# 02_TFT_LED.net
KiCad netlist of a schematic drawn in Altium Designer
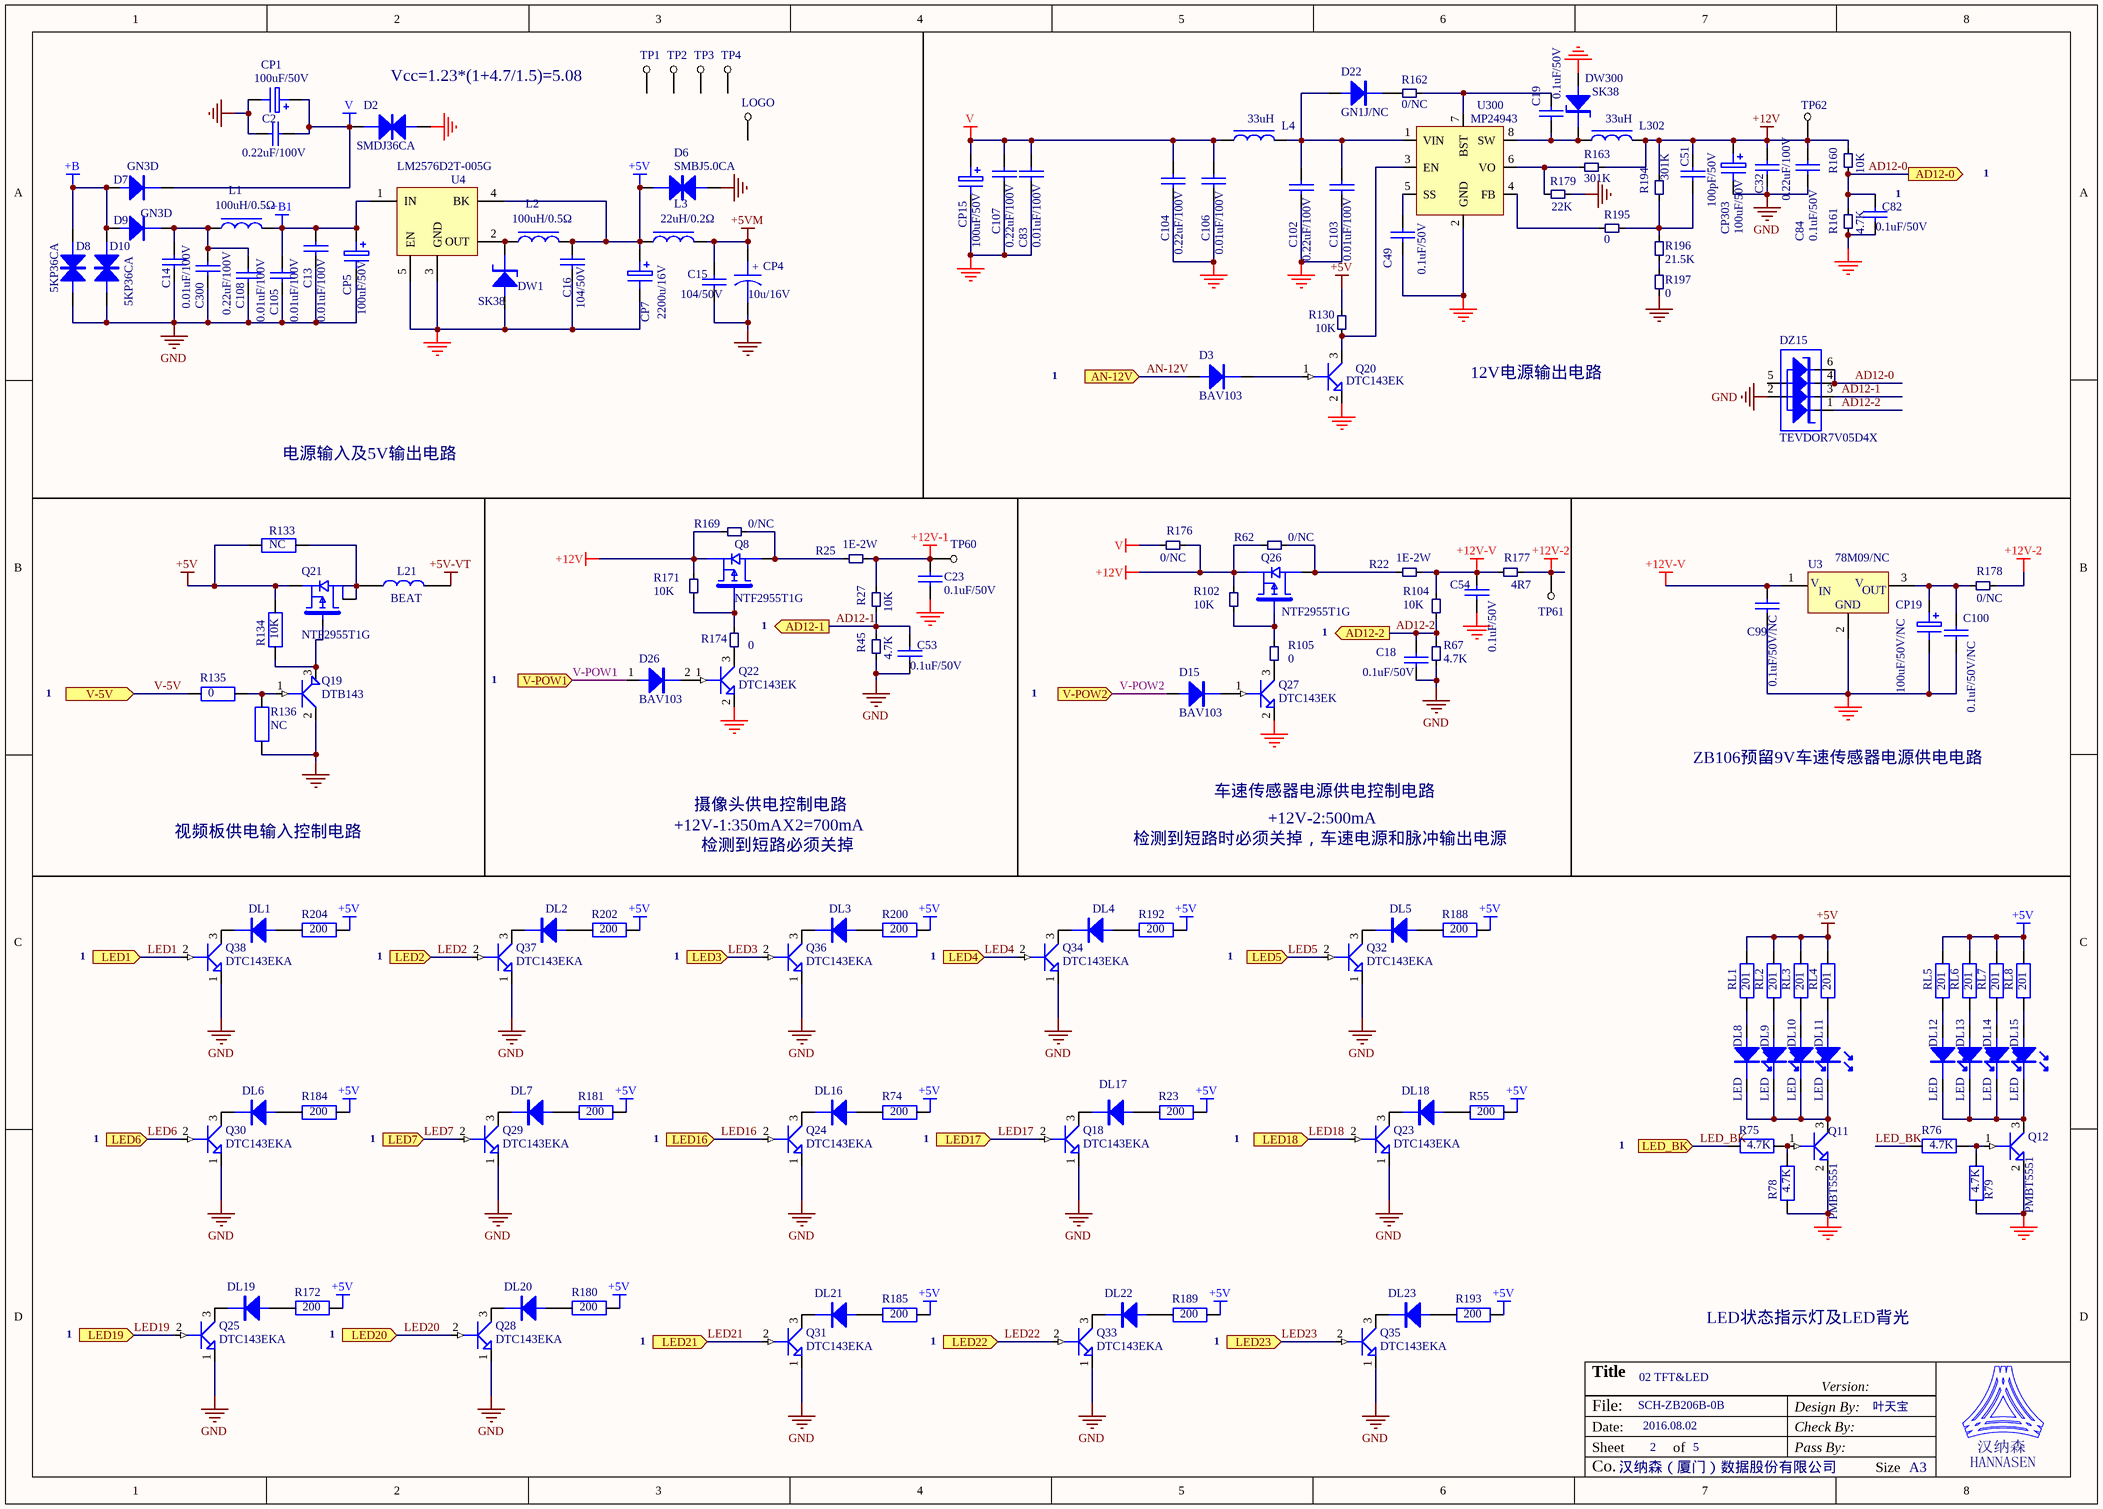
[diagram p0: 02 TFT&LED.SchDoc]

(export (version "E")
  (design (tool "Eeschema 10.0.6"))
  (components
    (comp (ref "C2")
      (value "0.22uF/100V")
      (footprint "CR1206")
      (description "Capacitor")
      (libsource (lib "*") (part "CAP"))
    )
    (comp (ref "C13")
      (value "0.01uF/100V")
      (footprint "CR0805")
      (description "Capacitor")
      (libsource (lib "*") (part "CAP"))
    )
    (comp (ref "C14")
      (value "0.01uF/100V")
      (footprint "CR0805")
      (description "Capacitor")
      (libsource (lib "*") (part "CAP"))
    )
    (comp (ref "C15")
      (value "104/50V")
      (footprint "CR0805")
      (description "Capacitor")
      (libsource (lib "*") (part "CAP"))
    )
    (comp (ref "C16")
      (value "104/50V")
      (footprint "CR0805")
      (description "Capacitor")
      (libsource (lib "*") (part "CAP"))
    )
    (comp (ref "C18")
      (value "0.1uF/50V")
      (footprint "CR0805")
      (description "Capacitor")
      (libsource (lib "*") (part "CAP"))
    )
    (comp (ref "C19")
      (value "0.1uF/50V")
      (footprint "CR0805")
      (description "Capacitor")
      (libsource (lib "*") (part "CAP"))
    )
    (comp (ref "C23")
      (value "0.1uF/50V")
      (footprint "CR0805")
      (description "Capacitor")
      (libsource (lib "*") (part "CAP"))
    )
    (comp (ref "C32")
      (value "0.22uF/100V")
      (footprint "CR1206")
      (description "Capacitor")
      (libsource (lib "*") (part "CAP"))
    )
    (comp (ref "C49")
      (value "0.1uF/50V")
      (footprint "CR0805")
      (description "Capacitor")
      (libsource (lib "*") (part "CAP"))
    )
    (comp (ref "C51")
      (value "100pF/50V")
      (footprint "CR0805")
      (description "Capacitor")
      (libsource (lib "*") (part "CAP"))
    )
    (comp (ref "C53")
      (value "0.1uF/50V")
      (footprint "CR0805")
      (description "Capacitor")
      (libsource (lib "*") (part "CAP"))
    )
    (comp (ref "C54")
      (value "0.1uF/50V")
      (footprint "CR0805")
      (description "Capacitor")
      (libsource (lib "*") (part "CAP"))
    )
    (comp (ref "C82")
      (value "0.1uF/50V")
      (footprint "CR0805")
      (description "Capacitor")
      (libsource (lib "*") (part "CAP"))
    )
    (comp (ref "C83")
      (value "0.01uF/100V")
      (footprint "CR0805")
      (description "Capacitor")
      (libsource (lib "*") (part "CAP"))
    )
    (comp (ref "C84")
      (value "0.1uF/50V")
      (footprint "CR0805")
      (description "Capacitor")
      (libsource (lib "*") (part "CAP"))
    )
    (comp (ref "C99")
      (value "0.1uF/50V/NC")
      (footprint "CR0805")
      (description "Capacitor")
      (libsource (lib "*") (part "CAP"))
    )
    (comp (ref "C100")
      (value "0.1uF/50V/NC")
      (footprint "CR0805")
      (description "Capacitor")
      (libsource (lib "*") (part "CAP"))
    )
    (comp (ref "C102")
      (value "0.22uF/100V")
      (footprint "CR1206")
      (description "Capacitor")
      (libsource (lib "*") (part "CAP"))
    )
    (comp (ref "C103")
      (value "0.01uF/100V")
      (footprint "CR0805")
      (description "Capacitor")
      (libsource (lib "*") (part "CAP"))
    )
    (comp (ref "C104")
      (value "0.22uF/100V")
      (footprint "CR1206")
      (description "Capacitor")
      (libsource (lib "*") (part "CAP"))
    )
    (comp (ref "C105")
      (value "0.01uF/100V")
      (footprint "CR0805")
      (description "Capacitor")
      (libsource (lib "*") (part "CAP"))
    )
    (comp (ref "C106")
      (value "0.01uF/100V")
      (footprint "CR0805")
      (description "Capacitor")
      (libsource (lib "*") (part "CAP"))
    )
    (comp (ref "C107")
      (value "0.22uF/100V")
      (footprint "CR1206")
      (description "Capacitor")
      (libsource (lib "*") (part "CAP"))
    )
    (comp (ref "C108")
      (value "0.01uF/100V")
      (footprint "CR0805")
      (description "Capacitor")
      (libsource (lib "*") (part "CAP"))
    )
    (comp (ref "C300")
      (value "0.22uF/100V")
      (footprint "CR1206")
      (description "Capacitor")
      (libsource (lib "*") (part "CAP"))
    )
    (comp (ref "CP1")
      (value "100uF/50V")
      (footprint "RB10")
      (description "电解电容")
      (libsource (lib "*") (part "ELECTRO1"))
    )
    (comp (ref "CP4")
      (value "10u/16V")
      (footprint "CE1206")
      (description "Capacitor")
      (libsource (lib "*") (part "CAPACITOR POL"))
    )
    (comp (ref "CP5")
      (value "100uF/50V")
      (footprint "RB5-1")
      (description "电解电容")
      (libsource (lib "*") (part "ELECTRO1"))
    )
    (comp (ref "CP7")
      (value "2200u/16V")
      (footprint "RB12.5")
      (description "电解电容")
      (libsource (lib "*") (part "ELECTRO1"))
    )
    (comp (ref "CP15")
      (value "100uF/50V")
      (footprint "RB5-1")
      (description "电解电容")
      (libsource (lib "*") (part "ELECTRO1"))
    )
    (comp (ref "CP19")
      (value "100uF/50V/NC")
      (footprint "RB5-1")
      (description "电解电容")
      (libsource (lib "*") (part "ELECTRO1"))
    )
    (comp (ref "CP303")
      (value "100uF/50V")
      (footprint "RB5-1")
      (description "电解电容")
      (libsource (lib "*") (part "ELECTRO1"))
    )
    (comp (ref "D2") (value "SMDJ36CA") (footprint "SMC-D") (libsource (lib "YDM-SQ-1SCH") (part "TVS")))
    (comp (ref "D3")
      (value "BAV103")
      (footprint "SOD-80C")
      (description "二极管")
      (libsource (lib "*") (part "DIODE"))
    )
    (comp (ref "D6") (value "SMBJ5.0CA") (footprint "SMB-D") (libsource (lib "YDM-SQ-1SCH") (part "TVS")))
    (comp (ref "D7")
      (value "GN3D")
      (footprint "SMC")
      (description "二极管")
      (libsource (lib "*") (part "DIODE"))
    )
    (comp (ref "D8") (value "5KP36CA") (footprint "D-17") (libsource (lib "*") (part "TVS")))
    (comp (ref "D9")
      (value "GN3D")
      (footprint "SMC")
      (description "二极管")
      (libsource (lib "*") (part "DIODE"))
    )
    (comp (ref "D10") (value "5KP36CA") (footprint "D-17") (libsource (lib "*") (part "TVS")))
    (comp (ref "D15")
      (value "BAV103")
      (footprint "SOD-80C")
      (description "二极管")
      (libsource (lib "*") (part "DIODE"))
    )
    (comp (ref "D22")
      (value "GN1J/NC")
      (footprint "SMA")
      (description "二极管")
      (libsource (lib "*") (part "DIODE"))
    )
    (comp (ref "D26")
      (value "BAV103")
      (footprint "SOD-80C")
      (description "二极管")
      (libsource (lib "") (part "DIODE_1"))
    )
    (comp (ref "DL1")
      (value "~")
      (footprint "LED1210")
      (description "贴片二极管")
      (libsource (lib "*") (part "DOS"))
    )
    (comp (ref "DL2")
      (value "~")
      (footprint "LED1210")
      (description "贴片二极管")
      (libsource (lib "*") (part "DOS"))
    )
    (comp (ref "DL3")
      (value "~")
      (footprint "LED1210")
      (description "贴片二极管")
      (libsource (lib "*") (part "DOS"))
    )
    (comp (ref "DL4")
      (value "~")
      (footprint "LED1210")
      (description "贴片二极管")
      (libsource (lib "*") (part "DOS"))
    )
    (comp (ref "DL5")
      (value "~")
      (footprint "LED1210")
      (description "贴片二极管")
      (libsource (lib "*") (part "DOS"))
    )
    (comp (ref "DL6")
      (value "~")
      (footprint "LED1210")
      (description "贴片二极管")
      (libsource (lib "*") (part "DOS"))
    )
    (comp (ref "DL7")
      (value "~")
      (footprint "LED1210")
      (description "贴片二极管")
      (libsource (lib "*") (part "DOS"))
    )
    (comp (ref "DL8")
      (value "LED")
      (footprint "LED1210")
      (description "贴片LED")
      (libsource (lib "*") (part "LED"))
    )
    (comp (ref "DL9")
      (value "LED")
      (footprint "LED1210")
      (description "贴片LED")
      (libsource (lib "*") (part "LED"))
    )
    (comp (ref "DL10")
      (value "LED")
      (footprint "LED1210")
      (description "贴片LED")
      (libsource (lib "*") (part "LED"))
    )
    (comp (ref "DL11")
      (value "LED")
      (footprint "LED1210")
      (description "贴片LED")
      (libsource (lib "*") (part "LED"))
    )
    (comp (ref "DL12")
      (value "LED")
      (footprint "LED1210")
      (description "贴片LED")
      (libsource (lib "*") (part "LED"))
    )
    (comp (ref "DL13")
      (value "LED")
      (footprint "LED1210")
      (description "贴片LED")
      (libsource (lib "*") (part "LED"))
    )
    (comp (ref "DL14")
      (value "LED")
      (footprint "LED1210")
      (description "贴片LED")
      (libsource (lib "*") (part "LED"))
    )
    (comp (ref "DL15")
      (value "LED")
      (footprint "LED1210")
      (description "贴片LED")
      (libsource (lib "*") (part "LED"))
    )
    (comp (ref "DL16")
      (value "~")
      (footprint "LED1210")
      (description "贴片二极管")
      (libsource (lib "*") (part "DOS"))
    )
    (comp (ref "DL17")
      (value "~")
      (footprint "LED1210")
      (description "贴片二极管")
      (libsource (lib "*") (part "DOS"))
    )
    (comp (ref "DL18")
      (value "~")
      (footprint "LED1210")
      (description "贴片二极管")
      (libsource (lib "*") (part "DOS"))
    )
    (comp (ref "DL19")
      (value "~")
      (footprint "LED1210")
      (description "贴片二极管")
      (libsource (lib "*") (part "DOS"))
    )
    (comp (ref "DL20")
      (value "~")
      (footprint "LED1210")
      (description "贴片二极管")
      (libsource (lib "*") (part "DOS"))
    )
    (comp (ref "DL21")
      (value "~")
      (footprint "LED1210")
      (description "贴片二极管")
      (libsource (lib "*") (part "DOS"))
    )
    (comp (ref "DL22")
      (value "~")
      (footprint "LED1210")
      (description "贴片二极管")
      (libsource (lib "*") (part "DOS"))
    )
    (comp (ref "DL23")
      (value "~")
      (footprint "LED1210")
      (description "贴片二极管")
      (libsource (lib "*") (part "DOS"))
    )
    (comp (ref "DW1")
      (value "SK38")
      (footprint "SMC")
      (description "稳压二极管")
      (libsource (lib "*") (part "DW"))
    )
    (comp (ref "DW300")
      (value "SK38")
      (footprint "SMC")
      (description "稳压二极管")
      (libsource (lib "*") (part "DW"))
    )
    (comp (ref "DZ15")
      (value "TEVDOR7V05D4X")
      (footprint "SOT-457")
      (description "二极管排")
      (libsource (lib "yibiaoschlib") (part "TEVDOR7V05D4X"))
    )
    (comp (ref "L1")
      (value "100uH/0.5Ω")
      (footprint "Ind-R13-7-100")
      (description "电感")
      (libsource (lib "*") (part "L"))
    )
    (comp (ref "L2")
      (value "100uH/0.5Ω")
      (footprint "Ind-R13-7-100")
      (description "电感")
      (libsource (lib "*") (part "L"))
    )
    (comp (ref "L3")
      (value "22uH/0.2Ω")
      (footprint "SS0603")
      (description "SS0603220ML")
      (libsource (lib "*") (part "L"))
    )
    (comp (ref "L4")
      (value "33uH")
      (footprint "Ind-R13-7-100")
      (description "电感")
      (libsource (lib "*") (part "L"))
    )
    (comp (ref "L21") (value "BEAT") (footprint "CR0805") (libsource (lib "YDM-SQ-1SCH") (part "BEAT")))
    (comp (ref "L302")
      (value "33uH")
      (footprint "Ind-R13-7-100")
      (description "电感")
      (libsource (lib "*") (part "L"))
    )
    (comp (ref "LOGO") (value "TP") (footprint "LOGO") (libsource (lib "YDM-SQ-1SCH") (part "TP")))
    (comp (ref "Q8")
      (value "NTF2955T1G")
      (footprint "SOT-223")
      (description "MOS")
      (libsource (lib "原理图库-1SCH") (part "MOS-P"))
    )
    (comp (ref "Q11")
      (value "PMBT5551")
      (footprint "SOT23")
      (description "PNP   三极管")
      (libsource (lib "原理图库-1SCH") (part "PMBT5551"))
    )
    (comp (ref "Q12")
      (value "PMBT5551")
      (footprint "SOT23")
      (description "PNP   三极管")
      (libsource (lib "原理图库-1SCH") (part "PMBT5551"))
    )
    (comp (ref "Q18")
      (value "DTC143EKA")
      (footprint "SMT3")
      (description "三极管-NPN带阻")
      (libsource (lib "HNS-SCH") (part "DTC143EKA"))
    )
    (comp (ref "Q19") (value "DTB143") (footprint "SOT23") (libsource (lib "原理图库-1SCH") (part "BCX53")))
    (comp (ref "Q20")
      (value "DTC143EK")
      (footprint "SOT23")
      (description "NPN")
      (libsource (lib "原理图库-1SCH") (part "DTC143"))
    )
    (comp (ref "Q21")
      (value "NTF2955T1G")
      (footprint "SOT-223")
      (description "MOS")
      (libsource (lib "yibiaoschlib") (part "NTF2955T1G"))
    )
    (comp (ref "Q22")
      (value "DTC143EK")
      (footprint "SOT23")
      (description "NPN")
      (libsource (lib "原理图库-1SCH") (part "DTC143"))
    )
    (comp (ref "Q23")
      (value "DTC143EKA")
      (footprint "SMT3")
      (description "三极管-NPN带阻")
      (libsource (lib "HNS-SCH") (part "DTC143EKA"))
    )
    (comp (ref "Q24")
      (value "DTC143EKA")
      (footprint "SMT3")
      (description "三极管-NPN带阻")
      (libsource (lib "HNS-SCH") (part "DTC143EKA"))
    )
    (comp (ref "Q25")
      (value "DTC143EKA")
      (footprint "SMT3")
      (description "三极管-NPN带阻")
      (libsource (lib "HNS-SCH") (part "DTC143EKA"))
    )
    (comp (ref "Q26")
      (value "NTF2955T1G")
      (footprint "SOT-223")
      (description "MOS")
      (libsource (lib "原理图库-1SCH") (part "MOS-P"))
    )
    (comp (ref "Q27")
      (value "DTC143EK")
      (footprint "SOT23")
      (description "NPN")
      (libsource (lib "原理图库-1SCH") (part "DTC143"))
    )
    (comp (ref "Q28")
      (value "DTC143EKA")
      (footprint "SMT3")
      (description "三极管-NPN带阻")
      (libsource (lib "HNS-SCH") (part "DTC143EKA"))
    )
    (comp (ref "Q29")
      (value "DTC143EKA")
      (footprint "SMT3")
      (description "三极管-NPN带阻")
      (libsource (lib "HNS-SCH") (part "DTC143EKA"))
    )
    (comp (ref "Q30")
      (value "DTC143EKA")
      (footprint "SMT3")
      (description "三极管-NPN带阻")
      (libsource (lib "HNS-SCH") (part "DTC143EKA"))
    )
    (comp (ref "Q31")
      (value "DTC143EKA")
      (footprint "SMT3")
      (description "三极管-NPN带阻")
      (libsource (lib "HNS-SCH") (part "DTC143EKA"))
    )
    (comp (ref "Q32")
      (value "DTC143EKA")
      (footprint "SMT3")
      (description "三极管-NPN带阻")
      (libsource (lib "HNS-SCH") (part "DTC143EKA"))
    )
    (comp (ref "Q33")
      (value "DTC143EKA")
      (footprint "SMT3")
      (description "三极管-NPN带阻")
      (libsource (lib "HNS-SCH") (part "DTC143EKA"))
    )
    (comp (ref "Q34")
      (value "DTC143EKA")
      (footprint "SMT3")
      (description "三极管-NPN带阻")
      (libsource (lib "HNS-SCH") (part "DTC143EKA"))
    )
    (comp (ref "Q35")
      (value "DTC143EKA")
      (footprint "SMT3")
      (description "三极管-NPN带阻")
      (libsource (lib "HNS-SCH") (part "DTC143EKA"))
    )
    (comp (ref "Q36")
      (value "DTC143EKA")
      (footprint "SMT3")
      (description "三极管-NPN带阻")
      (libsource (lib "HNS-SCH") (part "DTC143EKA"))
    )
    (comp (ref "Q37")
      (value "DTC143EKA")
      (footprint "SMT3")
      (description "三极管-NPN带阻")
      (libsource (lib "HNS-SCH") (part "DTC143EKA"))
    )
    (comp (ref "Q38")
      (value "DTC143EKA")
      (footprint "SMT3")
      (description "三极管-NPN带阻")
      (libsource (lib "HNS-SCH") (part "DTC143EKA"))
    )
    (comp (ref "R22")
      (value "1E-2W")
      (footprint "R2512")
      (description "贴片电阻")
      (libsource (lib "YDM-SQ-1SCH") (part "Resister mini"))
    )
    (comp (ref "R23")
      (value "200")
      (footprint "CR0805")
      (description "贴片电阻")
      (libsource (lib "YDM-SQ-1SCH") (part "RES"))
    )
    (comp (ref "R25")
      (value "1E-2W")
      (footprint "R2512")
      (description "贴片电阻")
      (libsource (lib "YDM-SQ-1SCH") (part "Resister mini"))
    )
    (comp (ref "R27")
      (value "10K")
      (footprint "CR0805")
      (description "贴片电阻")
      (libsource (lib "YDM-SQ-1SCH") (part "Resister mini"))
    )
    (comp (ref "R45")
      (value "4.7K")
      (footprint "CR0805")
      (description "贴片电阻")
      (libsource (lib "YDM-SQ-1SCH") (part "Resister mini"))
    )
    (comp (ref "R55")
      (value "200")
      (footprint "CR0805")
      (description "贴片电阻")
      (libsource (lib "YDM-SQ-1SCH") (part "RES"))
    )
    (comp (ref "R62")
      (value "0/NC")
      (footprint "CR1206")
      (description "贴片电阻")
      (libsource (lib "YDM-SQ-1SCH") (part "Resister mini"))
    )
    (comp (ref "R67")
      (value "4.7K")
      (footprint "CR0805")
      (description "贴片电阻")
      (libsource (lib "YDM-SQ-1SCH") (part "Resister mini"))
    )
    (comp (ref "R74")
      (value "200")
      (footprint "CR0805")
      (description "贴片电阻")
      (libsource (lib "YDM-SQ-1SCH") (part "RES"))
    )
    (comp (ref "R75")
      (value "4.7K")
      (footprint "CR0805")
      (description "贴片电阻")
      (libsource (lib "YDM-SQ-1SCH") (part "RES"))
    )
    (comp (ref "R76")
      (value "4.7K")
      (footprint "CR0805")
      (description "贴片电阻")
      (libsource (lib "YDM-SQ-1SCH") (part "RES"))
    )
    (comp (ref "R78")
      (value "4.7K")
      (footprint "CR0805")
      (description "贴片电阻")
      (libsource (lib "YDM-SQ-1SCH") (part "RES"))
    )
    (comp (ref "R79")
      (value "4.7K")
      (footprint "CR0805")
      (description "贴片电阻")
      (libsource (lib "YDM-SQ-1SCH") (part "RES"))
    )
    (comp (ref "R102")
      (value "10K")
      (footprint "CR0805")
      (description "贴片电阻")
      (libsource (lib "YDM-SQ-1SCH") (part "Resister mini"))
    )
    (comp (ref "R104")
      (value "10K")
      (footprint "CR0805")
      (description "贴片电阻")
      (libsource (lib "YDM-SQ-1SCH") (part "Resister mini"))
    )
    (comp (ref "R105")
      (value "0")
      (footprint "CR0805")
      (description "贴片电阻")
      (libsource (lib "YDM-SQ-1SCH") (part "Resister mini"))
    )
    (comp (ref "R130")
      (value "10K")
      (footprint "CR0805")
      (description "贴片电阻")
      (libsource (lib "YDM-SQ-1SCH") (part "Resister mini"))
    )
    (comp (ref "R133")
      (value "NC")
      (footprint "CR1206")
      (description "贴片电阻")
      (libsource (lib "YDM-SQ-1SCH") (part "RES"))
    )
    (comp (ref "R134")
      (value "10K")
      (footprint "CR0805")
      (description "贴片电阻")
      (libsource (lib "YDM-SQ-1SCH") (part "RES"))
    )
    (comp (ref "R135")
      (value "0")
      (footprint "CR0805")
      (description "贴片电阻")
      (libsource (lib "YDM-SQ-1SCH") (part "RES"))
    )
    (comp (ref "R136")
      (value "NC")
      (footprint "CR0805")
      (description "贴片电阻")
      (libsource (lib "YDM-SQ-1SCH") (part "RES"))
    )
    (comp (ref "R160")
      (value "10K")
      (footprint "CR0805")
      (description "贴片电阻")
      (libsource (lib "YDM-SQ-1SCH") (part "Resister mini"))
    )
    (comp (ref "R161")
      (value "4.7K")
      (footprint "CR0805")
      (description "贴片电阻")
      (libsource (lib "YDM-SQ-1SCH") (part "Resister mini"))
    )
    (comp (ref "R162")
      (value "0/NC")
      (footprint "CR0805")
      (description "贴片电阻")
      (libsource (lib "YDM-SQ-1SCH") (part "Resister mini"))
    )
    (comp (ref "R163")
      (value "301K")
      (footprint "CR0805")
      (description "贴片电阻")
      (libsource (lib "YDM-SQ-1SCH") (part "Resister mini"))
    )
    (comp (ref "R169")
      (value "0/NC")
      (footprint "CR1206")
      (description "贴片电阻")
      (libsource (lib "YDM-SQ-1SCH") (part "Resister mini"))
    )
    (comp (ref "R171")
      (value "10K")
      (footprint "CR0805")
      (description "贴片电阻")
      (libsource (lib "YDM-SQ-1SCH") (part "Resister mini"))
    )
    (comp (ref "R172")
      (value "200")
      (footprint "CR0805")
      (description "贴片电阻")
      (libsource (lib "YDM-SQ-1SCH") (part "RES"))
    )
    (comp (ref "R174")
      (value "0")
      (footprint "CR0805")
      (description "贴片电阻")
      (libsource (lib "YDM-SQ-1SCH") (part "Resister mini"))
    )
    (comp (ref "R176")
      (value "0/NC")
      (footprint "CR1206")
      (description "贴片电阻")
      (libsource (lib "YDM-SQ-1SCH") (part "Resister mini"))
    )
    (comp (ref "R177")
      (value "4R7")
      (footprint "CR1206")
      (description "贴片电阻")
      (libsource (lib "YDM-SQ-1SCH") (part "Resister mini"))
    )
    (comp (ref "R178")
      (value "0/NC")
      (footprint "CR1206")
      (description "贴片电阻")
      (libsource (lib "YDM-SQ-1SCH") (part "Resister mini"))
    )
    (comp (ref "R179")
      (value "22K")
      (footprint "CR0805")
      (description "贴片电阻")
      (libsource (lib "YDM-SQ-1SCH") (part "Resister mini"))
    )
    (comp (ref "R180")
      (value "200")
      (footprint "CR0805")
      (description "贴片电阻")
      (libsource (lib "YDM-SQ-1SCH") (part "RES"))
    )
    (comp (ref "R181")
      (value "200")
      (footprint "CR0805")
      (description "贴片电阻")
      (libsource (lib "YDM-SQ-1SCH") (part "RES"))
    )
    (comp (ref "R184")
      (value "200")
      (footprint "CR0805")
      (description "贴片电阻")
      (libsource (lib "YDM-SQ-1SCH") (part "RES"))
    )
    (comp (ref "R185")
      (value "200")
      (footprint "CR0805")
      (description "贴片电阻")
      (libsource (lib "YDM-SQ-1SCH") (part "RES"))
    )
    (comp (ref "R188")
      (value "200")
      (footprint "CR0805")
      (description "贴片电阻")
      (libsource (lib "YDM-SQ-1SCH") (part "RES"))
    )
    (comp (ref "R189")
      (value "200")
      (footprint "CR0805")
      (description "贴片电阻")
      (libsource (lib "YDM-SQ-1SCH") (part "RES"))
    )
    (comp (ref "R192")
      (value "200")
      (footprint "CR0805")
      (description "贴片电阻")
      (libsource (lib "YDM-SQ-1SCH") (part "RES"))
    )
    (comp (ref "R193")
      (value "200")
      (footprint "CR0805")
      (description "贴片电阻")
      (libsource (lib "YDM-SQ-1SCH") (part "RES"))
    )
    (comp (ref "R194")
      (value "301K")
      (footprint "CR0805")
      (description "贴片电阻")
      (libsource (lib "YDM-SQ-1SCH") (part "Resister mini"))
    )
    (comp (ref "R195")
      (value "0")
      (footprint "CR0805")
      (description "贴片电阻")
      (libsource (lib "YDM-SQ-1SCH") (part "Resister mini"))
    )
    (comp (ref "R196")
      (value "21.5K")
      (footprint "CR0805")
      (description "贴片电阻")
      (libsource (lib "YDM-SQ-1SCH") (part "Resister mini"))
    )
    (comp (ref "R197")
      (value "0")
      (footprint "CR0805")
      (description "贴片电阻")
      (libsource (lib "YDM-SQ-1SCH") (part "Resister mini"))
    )
    (comp (ref "R200")
      (value "200")
      (footprint "CR0805")
      (description "贴片电阻")
      (libsource (lib "YDM-SQ-1SCH") (part "RES"))
    )
    (comp (ref "R202")
      (value "200")
      (footprint "CR0805")
      (description "贴片电阻")
      (libsource (lib "YDM-SQ-1SCH") (part "RES"))
    )
    (comp (ref "R204")
      (value "200")
      (footprint "CR0805")
      (description "贴片电阻")
      (libsource (lib "YDM-SQ-1SCH") (part "RES"))
    )
    (comp (ref "RL1")
      (value "201")
      (footprint "CR0805")
      (description "贴片电阻")
      (libsource (lib "*") (part "RES"))
    )
    (comp (ref "RL2")
      (value "201")
      (footprint "CR0805")
      (description "贴片电阻")
      (libsource (lib "*") (part "RES"))
    )
    (comp (ref "RL3")
      (value "201")
      (footprint "CR0805")
      (description "贴片电阻")
      (libsource (lib "*") (part "RES"))
    )
    (comp (ref "RL4")
      (value "201")
      (footprint "CR0805")
      (description "贴片电阻")
      (libsource (lib "*") (part "RES"))
    )
    (comp (ref "RL5")
      (value "201")
      (footprint "CR0805")
      (description "贴片电阻")
      (libsource (lib "*") (part "RES"))
    )
    (comp (ref "RL6")
      (value "201")
      (footprint "CR0805")
      (description "贴片电阻")
      (libsource (lib "*") (part "RES"))
    )
    (comp (ref "RL7")
      (value "201")
      (footprint "CR0805")
      (description "贴片电阻")
      (libsource (lib "*") (part "RES"))
    )
    (comp (ref "RL8")
      (value "201")
      (footprint "CR0805")
      (description "贴片电阻")
      (libsource (lib "*") (part "RES"))
    )
    (comp (ref "TP1") (value "TP") (footprint "MARK") (libsource (lib "YDM-SQ-1SCH") (part "TP")))
    (comp (ref "TP2") (value "TP") (footprint "MARK") (libsource (lib "YDM-SQ-1SCH") (part "TP")))
    (comp (ref "TP3") (value "TP") (footprint "MARK") (libsource (lib "YDM-SQ-1SCH") (part "TP")))
    (comp (ref "TP4") (value "TP") (footprint "MARK") (libsource (lib "YDM-SQ-1SCH") (part "TP")))
    (comp (ref "TP60") (value "~") (footprint "TP") (libsource (lib "YDM-SQ-1SCH") (part "TP")))
    (comp (ref "TP61") (value "~") (footprint "TP") (libsource (lib "YDM-SQ-1SCH") (part "TP")))
    (comp (ref "TP62") (value "~") (footprint "TP") (libsource (lib "YDM-SQ-1SCH") (part "TP")))
    (comp (ref "U3")
      (value "78M09/NC")
      (footprint "DPAK")
      (description "IC-三端稳压")
      (libsource (lib "HNS-SCH") (part "78M12"))
    )
    (comp (ref "U4")
      (value "LM2576D2T-005G")
      (footprint "SOT-263-5")
      (description "DC/DC")
      (libsource (lib "*") (part "LDO_1"))
    )
    (comp (ref "U300")
      (value "MP24943")
      (footprint "SOIC8E")
      (description "IC-CAN DRIVER")
      (libsource (lib "原理图库-1SCH") (part "MP24943"))
    )
  )
  (nets
    (net (code "1") (name "+5V") (class "Default")
      (node (ref "C16") (pin "2") (pinfunction "2_2") (pintype "passive"))
      (node (ref "CP7") (pin "1") (pinfunction "1_1") (pintype "passive"))
      (node (ref "D6") (pin "1") (pinfunction "1_1") (pintype "passive"))
      (node (ref "L2") (pin "2") (pinfunction "2_2") (pintype "passive"))
      (node (ref "L3") (pin "1") (pinfunction "1_1") (pintype "passive"))
      (node (ref "Q21") (pin "3") (pinfunction "S_3") (pintype "passive"))
      (node (ref "R130") (pin "1") (pinfunction "1_1") (pintype "passive"))
      (node (ref "R133") (pin "1") (pinfunction "1_1") (pintype "passive"))
      (node (ref "R134") (pin "1") (pinfunction "1_1") (pintype "passive"))
      (node (ref "R172") (pin "2") (pinfunction "2_2") (pintype "passive"))
      (node (ref "R180") (pin "2") (pinfunction "2_2") (pintype "passive"))
      (node (ref "R181") (pin "2") (pinfunction "2_2") (pintype "passive"))
      (node (ref "R184") (pin "2") (pinfunction "2_2") (pintype "passive"))
      (node (ref "R185") (pin "2") (pinfunction "2_2") (pintype "passive"))
      (node (ref "R188") (pin "2") (pinfunction "2_2") (pintype "passive"))
      (node (ref "R189") (pin "2") (pinfunction "2_2") (pintype "passive"))
      (node (ref "R192") (pin "2") (pinfunction "2_2") (pintype "passive"))
      (node (ref "R193") (pin "2") (pinfunction "2_2") (pintype "passive"))
      (node (ref "R200") (pin "2") (pinfunction "2_2") (pintype "passive"))
      (node (ref "R202") (pin "2") (pinfunction "2_2") (pintype "passive"))
      (node (ref "R204") (pin "2") (pinfunction "2_2") (pintype "passive"))
      (node (ref "R23") (pin "2") (pinfunction "2_2") (pintype "passive"))
      (node (ref "R55") (pin "2") (pinfunction "2_2") (pintype "passive"))
      (node (ref "R74") (pin "2") (pinfunction "2_2") (pintype "passive"))
      (node (ref "RL1") (pin "1") (pinfunction "1_1") (pintype "passive"))
      (node (ref "RL2") (pin "1") (pinfunction "1_1") (pintype "passive"))
      (node (ref "RL3") (pin "1") (pinfunction "1_1") (pintype "passive"))
      (node (ref "RL4") (pin "1") (pinfunction "1_1") (pintype "passive"))
      (node (ref "RL5") (pin "1") (pinfunction "1_1") (pintype "passive"))
      (node (ref "RL6") (pin "1") (pinfunction "1_1") (pintype "passive"))
      (node (ref "RL7") (pin "1") (pinfunction "1_1") (pintype "passive"))
      (node (ref "RL8") (pin "1") (pinfunction "1_1") (pintype "passive"))
      (node (ref "U4") (pin "4") (pinfunction "BK_4") (pintype "passive"))
    )
    (net (code "2") (name "+5V-VT") (class "Default")
      (node (ref "L21") (pin "2") (pinfunction "2_2") (pintype "passive"))
    )
    (net (code "3") (name "+5VM") (class "Default")
      (node (ref "C15") (pin "1") (pinfunction "1_1") (pintype "passive"))
      (node (ref "CP4") (pin "1") (pinfunction "1_1") (pintype "passive"))
      (node (ref "L3") (pin "2") (pinfunction "2_2") (pintype "passive"))
    )
    (net (code "4") (name "+12V") (class "Default")
      (node (ref "C32") (pin "2") (pinfunction "2_2") (pintype "passive"))
      (node (ref "C51") (pin "2") (pinfunction "2_2") (pintype "passive"))
      (node (ref "C84") (pin "2") (pinfunction "2_2") (pintype "passive"))
      (node (ref "CP303") (pin "1") (pinfunction "1_1") (pintype "passive"))
      (node (ref "L302") (pin "2") (pinfunction "2_2") (pintype "passive"))
      (node (ref "Q26") (pin "3") (pintype "passive"))
      (node (ref "Q8") (pin "3") (pintype "passive"))
      (node (ref "R102") (pin "2") (pinfunction "2_2") (pintype "passive"))
      (node (ref "R160") (pin "2") (pinfunction "2_2") (pintype "passive"))
      (node (ref "R163") (pin "2") (pinfunction "2_2") (pintype "passive"))
      (node (ref "R169") (pin "1") (pinfunction "1_1") (pintype "passive"))
      (node (ref "R171") (pin "2") (pinfunction "2_2") (pintype "passive"))
      (node (ref "R176") (pin "2") (pinfunction "2_2") (pintype "passive"))
      (node (ref "R194") (pin "1") (pinfunction "1_1") (pintype "passive"))
      (node (ref "R62") (pin "1") (pinfunction "1_1") (pintype "passive"))
      (node (ref "TP62") (pin "1") (pinfunction "1_1") (pintype "passive"))
    )
    (net (code "5") (name "+12V-1") (class "Default")
      (node (ref "C23") (pin "1") (pinfunction "1_1") (pintype "passive"))
      (node (ref "R25") (pin "2") (pinfunction "2_2") (pintype "passive"))
      (node (ref "R27") (pin "2") (pinfunction "2_2") (pintype "passive"))
      (node (ref "TP60") (pin "1") (pinfunction "1_1") (pintype "passive"))
    )
    (net (code "6") (name "+12V-2") (class "Default")
      (node (ref "R177") (pin "2") (pinfunction "2_2") (pintype "passive"))
      (node (ref "R178") (pin "2") (pinfunction "2_2") (pintype "passive"))
      (node (ref "TP61") (pin "1") (pinfunction "1_1") (pintype "passive"))
    )
    (net (code "7") (name "+12V-V") (class "Default")
      (node (ref "C54") (pin "1") (pinfunction "1_1") (pintype "passive"))
      (node (ref "C99") (pin "2") (pinfunction "2_2") (pintype "passive"))
      (node (ref "R104") (pin "2") (pinfunction "2_2") (pintype "passive"))
      (node (ref "R177") (pin "1") (pinfunction "1_1") (pintype "passive"))
      (node (ref "R22") (pin "2") (pinfunction "2_2") (pintype "passive"))
      (node (ref "U3") (pin "1") (pinfunction "VIN_1") (pintype "passive"))
    )
    (net (code "8") (name "+B") (class "Default")
      (node (ref "D10") (pin "1") (pinfunction "1_1") (pintype "passive"))
      (node (ref "D7") (pin "1") (pinfunction "A_1") (pintype "passive"))
      (node (ref "D8") (pin "1") (pinfunction "1_1") (pintype "passive"))
      (node (ref "D9") (pin "1") (pinfunction "A_1") (pintype "passive"))
    )
    (net (code "9") (name "+B1") (class "Default")
      (node (ref "C105") (pin "2") (pinfunction "2_2") (pintype "passive"))
      (node (ref "C13") (pin "2") (pinfunction "2_2") (pintype "passive"))
      (node (ref "CP5") (pin "1") (pinfunction "1_1") (pintype "passive"))
      (node (ref "L1") (pin "2") (pinfunction "2_2") (pintype "passive"))
      (node (ref "U4") (pin "1") (pinfunction "IN_1") (pintype "passive"))
    )
    (net (code "10") (name "/AD12-0") (class "Default")
      (node (ref "C82") (pin "2") (pinfunction "2_2") (pintype "passive"))
      (node (ref "DZ15") (pin "4") (pintype "passive"))
      (node (ref "DZ15") (pin "6") (pintype "passive"))
      (node (ref "R160") (pin "1") (pinfunction "1_1") (pintype "passive"))
      (node (ref "R161") (pin "2") (pinfunction "2_2") (pintype "passive"))
    )
    (net (code "11") (name "/AD12-1") (class "Default")
      (node (ref "C53") (pin "2") (pinfunction "2_2") (pintype "passive"))
      (node (ref "DZ15") (pin "3") (pintype "passive"))
      (node (ref "R27") (pin "1") (pinfunction "1_1") (pintype "passive"))
      (node (ref "R45") (pin "2") (pinfunction "2_2") (pintype "passive"))
    )
    (net (code "12") (name "/AD12-2") (class "Default")
      (node (ref "C18") (pin "2") (pinfunction "2_2") (pintype "passive"))
      (node (ref "DZ15") (pin "1") (pintype "passive"))
      (node (ref "R104") (pin "1") (pinfunction "1_1") (pintype "passive"))
      (node (ref "R67") (pin "2") (pinfunction "2_2") (pintype "passive"))
    )
    (net (code "13") (name "/AN-12V") (class "Default")
      (node (ref "D3") (pin "1") (pinfunction "A_1") (pintype "passive"))
    )
    (net (code "14") (name "/LED1") (class "Default")
      (node (ref "Q38") (pin "2") (pinfunction "in_2") (pintype "input"))
    )
    (net (code "15") (name "/LED2") (class "Default")
      (node (ref "Q37") (pin "2") (pinfunction "in_2") (pintype "input"))
    )
    (net (code "16") (name "/LED3") (class "Default")
      (node (ref "Q36") (pin "2") (pinfunction "in_2") (pintype "input"))
    )
    (net (code "17") (name "/LED4") (class "Default")
      (node (ref "Q34") (pin "2") (pinfunction "in_2") (pintype "input"))
    )
    (net (code "18") (name "/LED5") (class "Default")
      (node (ref "Q32") (pin "2") (pinfunction "in_2") (pintype "input"))
    )
    (net (code "19") (name "/LED6") (class "Default")
      (node (ref "Q30") (pin "2") (pinfunction "in_2") (pintype "input"))
    )
    (net (code "20") (name "/LED7") (class "Default")
      (node (ref "Q29") (pin "2") (pinfunction "in_2") (pintype "input"))
    )
    (net (code "21") (name "/LED16") (class "Default")
      (node (ref "Q24") (pin "2") (pinfunction "in_2") (pintype "input"))
    )
    (net (code "22") (name "/LED17") (class "Default")
      (node (ref "Q18") (pin "2") (pinfunction "in_2") (pintype "input"))
    )
    (net (code "23") (name "/LED18") (class "Default")
      (node (ref "Q23") (pin "2") (pinfunction "in_2") (pintype "input"))
    )
    (net (code "24") (name "/LED19") (class "Default")
      (node (ref "Q25") (pin "2") (pinfunction "in_2") (pintype "input"))
    )
    (net (code "25") (name "/LED20") (class "Default")
      (node (ref "Q28") (pin "2") (pinfunction "in_2") (pintype "input"))
    )
    (net (code "26") (name "/LED21") (class "Default")
      (node (ref "Q31") (pin "2") (pinfunction "in_2") (pintype "input"))
    )
    (net (code "27") (name "/LED22") (class "Default")
      (node (ref "Q33") (pin "2") (pinfunction "in_2") (pintype "input"))
    )
    (net (code "28") (name "/LED23") (class "Default")
      (node (ref "Q35") (pin "2") (pinfunction "in_2") (pintype "input"))
    )
    (net (code "29") (name "/LED_BK") (class "Default")
      (node (ref "R75") (pin "1") (pinfunction "1_1") (pintype "passive"))
      (node (ref "R76") (pin "1") (pinfunction "1_1") (pintype "passive"))
    )
    (net (code "30") (name "/V-5V") (class "Default")
      (node (ref "R135") (pin "1") (pinfunction "1_1") (pintype "passive"))
    )
    (net (code "31") (name "/V-POW1") (class "Default")
      (node (ref "D26") (pin "1") (pinfunction "A_1") (pintype "passive"))
    )
    (net (code "32") (name "/V-POW2") (class "Default")
      (node (ref "D15") (pin "1") (pinfunction "A_1") (pintype "passive"))
    )
    (net (code "33") (name "GND") (class "Default")
      (node (ref "C100") (pin "2") (pinfunction "2_2") (pintype "passive"))
      (node (ref "C102") (pin "1") (pinfunction "1_1") (pintype "passive"))
      (node (ref "C103") (pin "1") (pinfunction "1_1") (pintype "passive"))
      (node (ref "C104") (pin "1") (pinfunction "1_1") (pintype "passive"))
      (node (ref "C105") (pin "1") (pinfunction "1_1") (pintype "passive"))
      (node (ref "C106") (pin "1") (pinfunction "1_1") (pintype "passive"))
      (node (ref "C107") (pin "1") (pinfunction "1_1") (pintype "passive"))
      (node (ref "C108") (pin "1") (pinfunction "1_1") (pintype "passive"))
      (node (ref "C13") (pin "1") (pinfunction "1_1") (pintype "passive"))
      (node (ref "C14") (pin "1") (pinfunction "1_1") (pintype "passive"))
      (node (ref "C15") (pin "2") (pinfunction "2_2") (pintype "passive"))
      (node (ref "C16") (pin "1") (pinfunction "1_1") (pintype "passive"))
      (node (ref "C18") (pin "1") (pinfunction "1_1") (pintype "passive"))
      (node (ref "C2") (pin "1") (pinfunction "1_1") (pintype "passive"))
      (node (ref "C23") (pin "2") (pinfunction "2_2") (pintype "passive"))
      (node (ref "C300") (pin "1") (pinfunction "1_1") (pintype "passive"))
      (node (ref "C32") (pin "1") (pinfunction "1_1") (pintype "passive"))
      (node (ref "C49") (pin "1") (pinfunction "1_1") (pintype "passive"))
      (node (ref "C53") (pin "1") (pinfunction "1_1") (pintype "passive"))
      (node (ref "C54") (pin "2") (pinfunction "2_2") (pintype "passive"))
      (node (ref "C82") (pin "1") (pinfunction "1_1") (pintype "passive"))
      (node (ref "C83") (pin "1") (pinfunction "1_1") (pintype "passive"))
      (node (ref "C84") (pin "1") (pinfunction "1_1") (pintype "passive"))
      (node (ref "C99") (pin "1") (pinfunction "1_1") (pintype "passive"))
      (node (ref "CP1") (pin "2") (pinfunction "2_2") (pintype "passive"))
      (node (ref "CP15") (pin "2") (pinfunction "2_2") (pintype "passive"))
      (node (ref "CP19") (pin "2") (pinfunction "2_2") (pintype "passive"))
      (node (ref "CP303") (pin "2") (pinfunction "2_2") (pintype "passive"))
      (node (ref "CP4") (pin "2") (pinfunction "2_2") (pintype "passive"))
      (node (ref "CP5") (pin "2") (pinfunction "2_2") (pintype "passive"))
      (node (ref "CP7") (pin "2") (pinfunction "2_2") (pintype "passive"))
      (node (ref "D10") (pin "2") (pinfunction "2_2") (pintype "passive"))
      (node (ref "D2") (pin "2") (pinfunction "2_2") (pintype "passive"))
      (node (ref "D6") (pin "2") (pinfunction "2_2") (pintype "passive"))
      (node (ref "D8") (pin "2") (pinfunction "2_2") (pintype "passive"))
      (node (ref "DW1") (pin "1") (pinfunction "A_1") (pintype "passive"))
      (node (ref "DW300") (pin "1") (pinfunction "A_1") (pintype "passive"))
      (node (ref "DZ15") (pin "2") (pintype "passive"))
      (node (ref "Q11") (pin "2") (pinfunction "E_2") (pintype "passive"))
      (node (ref "Q12") (pin "2") (pinfunction "E_2") (pintype "passive"))
      (node (ref "Q18") (pin "1") (pinfunction "gnd_1") (pintype "passive"))
      (node (ref "Q19") (pin "2") (pinfunction "c_2") (pintype "passive"))
      (node (ref "Q20") (pin "2") (pinfunction "gnd_2") (pintype "passive"))
      (node (ref "Q22") (pin "2") (pinfunction "gnd_2") (pintype "passive"))
      (node (ref "Q23") (pin "1") (pinfunction "gnd_1") (pintype "passive"))
      (node (ref "Q24") (pin "1") (pinfunction "gnd_1") (pintype "passive"))
      (node (ref "Q25") (pin "1") (pinfunction "gnd_1") (pintype "passive"))
      (node (ref "Q27") (pin "2") (pinfunction "gnd_2") (pintype "passive"))
      (node (ref "Q28") (pin "1") (pinfunction "gnd_1") (pintype "passive"))
      (node (ref "Q29") (pin "1") (pinfunction "gnd_1") (pintype "passive"))
      (node (ref "Q30") (pin "1") (pinfunction "gnd_1") (pintype "passive"))
      (node (ref "Q31") (pin "1") (pinfunction "gnd_1") (pintype "passive"))
      (node (ref "Q32") (pin "1") (pinfunction "gnd_1") (pintype "passive"))
      (node (ref "Q33") (pin "1") (pinfunction "gnd_1") (pintype "passive"))
      (node (ref "Q34") (pin "1") (pinfunction "gnd_1") (pintype "passive"))
      (node (ref "Q35") (pin "1") (pinfunction "gnd_1") (pintype "passive"))
      (node (ref "Q36") (pin "1") (pinfunction "gnd_1") (pintype "passive"))
      (node (ref "Q37") (pin "1") (pinfunction "gnd_1") (pintype "passive"))
      (node (ref "Q38") (pin "1") (pinfunction "gnd_1") (pintype "passive"))
      (node (ref "R136") (pin "1") (pinfunction "1_1") (pintype "passive"))
      (node (ref "R161") (pin "1") (pinfunction "1_1") (pintype "passive"))
      (node (ref "R179") (pin "1") (pinfunction "1_1") (pintype "passive"))
      (node (ref "R197") (pin "2") (pinfunction "2_2") (pintype "passive"))
      (node (ref "R45") (pin "1") (pinfunction "1_1") (pintype "passive"))
      (node (ref "R67") (pin "1") (pinfunction "1_1") (pintype "passive"))
      (node (ref "R78") (pin "2") (pinfunction "2_2") (pintype "passive"))
      (node (ref "R79") (pin "2") (pinfunction "2_2") (pintype "passive"))
      (node (ref "U3") (pin "2") (pinfunction "GND_2") (pintype "passive"))
      (node (ref "U300") (pin "2") (pinfunction "GND_2") (pintype "passive"))
      (node (ref "U4") (pin "3") (pinfunction "GND_3") (pintype "passive"))
      (node (ref "U4") (pin "5") (pinfunction "EN_5") (pintype "passive"))
    )
    (net (code "34") (name "Net-(C51-Pad1)") (class "Default")
      (node (ref "C51") (pin "1") (pinfunction "1_1") (pintype "passive"))
      (node (ref "R194") (pin "2") (pinfunction "2_2") (pintype "passive"))
      (node (ref "R195") (pin "1") (pinfunction "1_1") (pintype "passive"))
      (node (ref "R196") (pin "1") (pinfunction "1_1") (pintype "passive"))
    )
    (net (code "35") (name "Net-(D3-K)") (class "Default")
      (node (ref "D3") (pin "2") (pinfunction "K_2") (pintype "passive"))
      (node (ref "Q20") (pin "1") (pinfunction "in_1") (pintype "input"))
    )
    (net (code "36") (name "Net-(D9-K)") (class "Default")
      (node (ref "C108") (pin "2") (pinfunction "2_2") (pintype "passive"))
      (node (ref "C14") (pin "2") (pinfunction "2_2") (pintype "passive"))
      (node (ref "C300") (pin "2") (pinfunction "2_2") (pintype "passive"))
      (node (ref "D9") (pin "2") (pinfunction "K_2") (pintype "passive"))
      (node (ref "L1") (pin "1") (pinfunction "1_1") (pintype "passive"))
    )
    (net (code "37") (name "Net-(D15-K)") (class "Default")
      (node (ref "D15") (pin "2") (pinfunction "K_2") (pintype "passive"))
      (node (ref "Q27") (pin "1") (pinfunction "in_1") (pintype "input"))
    )
    (net (code "38") (name "Net-(D22-A)") (class "Default")
      (node (ref "C102") (pin "2") (pinfunction "2_2") (pintype "passive"))
      (node (ref "C103") (pin "2") (pinfunction "2_2") (pintype "passive"))
      (node (ref "D22") (pin "1") (pinfunction "A_1") (pintype "passive"))
      (node (ref "L4") (pin "2") (pinfunction "2_2") (pintype "passive"))
      (node (ref "U300") (pin "1") (pinfunction "VIN_1") (pintype "passive"))
    )
    (net (code "39") (name "Net-(D22-K)") (class "Default")
      (node (ref "D22") (pin "2") (pinfunction "K_2") (pintype "passive"))
      (node (ref "R162") (pin "2") (pinfunction "2_2") (pintype "passive"))
    )
    (net (code "40") (name "Net-(D26-K)") (class "Default")
      (node (ref "D26") (pin "2") (pinfunction "K_2") (pintype "passive"))
      (node (ref "Q22") (pin "1") (pinfunction "in_1") (pintype "input"))
    )
    (net (code "41") (name "Net-(DL1-A)") (class "Default")
      (node (ref "DL1") (pin "1") (pinfunction "A_1") (pintype "passive"))
      (node (ref "R204") (pin "1") (pinfunction "1_1") (pintype "passive"))
    )
    (net (code "42") (name "Net-(DL1-K)") (class "Default")
      (node (ref "DL1") (pin "2") (pinfunction "K_2") (pintype "passive"))
      (node (ref "Q38") (pin "3") (pinfunction "out_3") (pintype "passive"))
    )
    (net (code "43") (name "Net-(DL2-A)") (class "Default")
      (node (ref "DL2") (pin "1") (pinfunction "A_1") (pintype "passive"))
      (node (ref "R202") (pin "1") (pinfunction "1_1") (pintype "passive"))
    )
    (net (code "44") (name "Net-(DL2-K)") (class "Default")
      (node (ref "DL2") (pin "2") (pinfunction "K_2") (pintype "passive"))
      (node (ref "Q37") (pin "3") (pinfunction "out_3") (pintype "passive"))
    )
    (net (code "45") (name "Net-(DL3-A)") (class "Default")
      (node (ref "DL3") (pin "1") (pinfunction "A_1") (pintype "passive"))
      (node (ref "R200") (pin "1") (pinfunction "1_1") (pintype "passive"))
    )
    (net (code "46") (name "Net-(DL3-K)") (class "Default")
      (node (ref "DL3") (pin "2") (pinfunction "K_2") (pintype "passive"))
      (node (ref "Q36") (pin "3") (pinfunction "out_3") (pintype "passive"))
    )
    (net (code "47") (name "Net-(DL4-A)") (class "Default")
      (node (ref "DL4") (pin "1") (pinfunction "A_1") (pintype "passive"))
      (node (ref "R192") (pin "1") (pinfunction "1_1") (pintype "passive"))
    )
    (net (code "48") (name "Net-(DL4-K)") (class "Default")
      (node (ref "DL4") (pin "2") (pinfunction "K_2") (pintype "passive"))
      (node (ref "Q34") (pin "3") (pinfunction "out_3") (pintype "passive"))
    )
    (net (code "49") (name "Net-(DL5-A)") (class "Default")
      (node (ref "DL5") (pin "1") (pinfunction "A_1") (pintype "passive"))
      (node (ref "R188") (pin "1") (pinfunction "1_1") (pintype "passive"))
    )
    (net (code "50") (name "Net-(DL5-K)") (class "Default")
      (node (ref "DL5") (pin "2") (pinfunction "K_2") (pintype "passive"))
      (node (ref "Q32") (pin "3") (pinfunction "out_3") (pintype "passive"))
    )
    (net (code "51") (name "Net-(DL6-A)") (class "Default")
      (node (ref "DL6") (pin "1") (pinfunction "A_1") (pintype "passive"))
      (node (ref "R184") (pin "1") (pinfunction "1_1") (pintype "passive"))
    )
    (net (code "52") (name "Net-(DL6-K)") (class "Default")
      (node (ref "DL6") (pin "2") (pinfunction "K_2") (pintype "passive"))
      (node (ref "Q30") (pin "3") (pinfunction "out_3") (pintype "passive"))
    )
    (net (code "53") (name "Net-(DL7-A)") (class "Default")
      (node (ref "DL7") (pin "1") (pinfunction "A_1") (pintype "passive"))
      (node (ref "R181") (pin "1") (pinfunction "1_1") (pintype "passive"))
    )
    (net (code "54") (name "Net-(DL7-K)") (class "Default")
      (node (ref "DL7") (pin "2") (pinfunction "K_2") (pintype "passive"))
      (node (ref "Q29") (pin "3") (pinfunction "out_3") (pintype "passive"))
    )
    (net (code "55") (name "Net-(DL8-Pad1)") (class "Default")
      (node (ref "DL8") (pin "1") (pinfunction "1_1") (pintype "passive"))
      (node (ref "RL1") (pin "2") (pinfunction "2_2") (pintype "passive"))
    )
    (net (code "56") (name "Net-(DL9-Pad1)") (class "Default")
      (node (ref "DL9") (pin "1") (pinfunction "1_1") (pintype "passive"))
      (node (ref "RL2") (pin "2") (pinfunction "2_2") (pintype "passive"))
    )
    (net (code "57") (name "Net-(DL10-Pad1)") (class "Default")
      (node (ref "DL10") (pin "1") (pinfunction "1_1") (pintype "passive"))
      (node (ref "RL3") (pin "2") (pinfunction "2_2") (pintype "passive"))
    )
    (net (code "58") (name "Net-(DL11-Pad1)") (class "Default")
      (node (ref "DL11") (pin "1") (pinfunction "1_1") (pintype "passive"))
      (node (ref "RL4") (pin "2") (pinfunction "2_2") (pintype "passive"))
    )
    (net (code "59") (name "Net-(DL12-Pad1)") (class "Default")
      (node (ref "DL12") (pin "1") (pinfunction "1_1") (pintype "passive"))
      (node (ref "RL5") (pin "2") (pinfunction "2_2") (pintype "passive"))
    )
    (net (code "60") (name "Net-(DL13-Pad1)") (class "Default")
      (node (ref "DL13") (pin "1") (pinfunction "1_1") (pintype "passive"))
      (node (ref "RL6") (pin "2") (pinfunction "2_2") (pintype "passive"))
    )
    (net (code "61") (name "Net-(DL14-Pad1)") (class "Default")
      (node (ref "DL14") (pin "1") (pinfunction "1_1") (pintype "passive"))
      (node (ref "RL7") (pin "2") (pinfunction "2_2") (pintype "passive"))
    )
    (net (code "62") (name "Net-(DL15-Pad1)") (class "Default")
      (node (ref "DL15") (pin "1") (pinfunction "1_1") (pintype "passive"))
      (node (ref "RL8") (pin "2") (pinfunction "2_2") (pintype "passive"))
    )
    (net (code "63") (name "Net-(DL16-A)") (class "Default")
      (node (ref "DL16") (pin "1") (pinfunction "A_1") (pintype "passive"))
      (node (ref "R74") (pin "1") (pinfunction "1_1") (pintype "passive"))
    )
    (net (code "64") (name "Net-(DL16-K)") (class "Default")
      (node (ref "DL16") (pin "2") (pinfunction "K_2") (pintype "passive"))
      (node (ref "Q24") (pin "3") (pinfunction "out_3") (pintype "passive"))
    )
    (net (code "65") (name "Net-(DL17-A)") (class "Default")
      (node (ref "DL17") (pin "1") (pinfunction "A_1") (pintype "passive"))
      (node (ref "R23") (pin "1") (pinfunction "1_1") (pintype "passive"))
    )
    (net (code "66") (name "Net-(DL17-K)") (class "Default")
      (node (ref "DL17") (pin "2") (pinfunction "K_2") (pintype "passive"))
      (node (ref "Q18") (pin "3") (pinfunction "out_3") (pintype "passive"))
    )
    (net (code "67") (name "Net-(DL18-A)") (class "Default")
      (node (ref "DL18") (pin "1") (pinfunction "A_1") (pintype "passive"))
      (node (ref "R55") (pin "1") (pinfunction "1_1") (pintype "passive"))
    )
    (net (code "68") (name "Net-(DL18-K)") (class "Default")
      (node (ref "DL18") (pin "2") (pinfunction "K_2") (pintype "passive"))
      (node (ref "Q23") (pin "3") (pinfunction "out_3") (pintype "passive"))
    )
    (net (code "69") (name "Net-(DL19-A)") (class "Default")
      (node (ref "DL19") (pin "1") (pinfunction "A_1") (pintype "passive"))
      (node (ref "R172") (pin "1") (pinfunction "1_1") (pintype "passive"))
    )
    (net (code "70") (name "Net-(DL19-K)") (class "Default")
      (node (ref "DL19") (pin "2") (pinfunction "K_2") (pintype "passive"))
      (node (ref "Q25") (pin "3") (pinfunction "out_3") (pintype "passive"))
    )
    (net (code "71") (name "Net-(DL20-A)") (class "Default")
      (node (ref "DL20") (pin "1") (pinfunction "A_1") (pintype "passive"))
      (node (ref "R180") (pin "1") (pinfunction "1_1") (pintype "passive"))
    )
    (net (code "72") (name "Net-(DL20-K)") (class "Default")
      (node (ref "DL20") (pin "2") (pinfunction "K_2") (pintype "passive"))
      (node (ref "Q28") (pin "3") (pinfunction "out_3") (pintype "passive"))
    )
    (net (code "73") (name "Net-(DL21-A)") (class "Default")
      (node (ref "DL21") (pin "1") (pinfunction "A_1") (pintype "passive"))
      (node (ref "R185") (pin "1") (pinfunction "1_1") (pintype "passive"))
    )
    (net (code "74") (name "Net-(DL21-K)") (class "Default")
      (node (ref "DL21") (pin "2") (pinfunction "K_2") (pintype "passive"))
      (node (ref "Q31") (pin "3") (pinfunction "out_3") (pintype "passive"))
    )
    (net (code "75") (name "Net-(DL22-A)") (class "Default")
      (node (ref "DL22") (pin "1") (pinfunction "A_1") (pintype "passive"))
      (node (ref "R189") (pin "1") (pinfunction "1_1") (pintype "passive"))
    )
    (net (code "76") (name "Net-(DL22-K)") (class "Default")
      (node (ref "DL22") (pin "2") (pinfunction "K_2") (pintype "passive"))
      (node (ref "Q33") (pin "3") (pinfunction "out_3") (pintype "passive"))
    )
    (net (code "77") (name "Net-(DL23-A)") (class "Default")
      (node (ref "DL23") (pin "1") (pinfunction "A_1") (pintype "passive"))
      (node (ref "R193") (pin "1") (pinfunction "1_1") (pintype "passive"))
    )
    (net (code "78") (name "Net-(DL23-K)") (class "Default")
      (node (ref "DL23") (pin "2") (pinfunction "K_2") (pintype "passive"))
      (node (ref "Q35") (pin "3") (pinfunction "out_3") (pintype "passive"))
    )
    (net (code "79") (name "Net-(DW1-K)") (class "Default")
      (node (ref "DW1") (pin "2") (pinfunction "K_2") (pintype "passive"))
      (node (ref "L2") (pin "1") (pinfunction "1_1") (pintype "passive"))
      (node (ref "U4") (pin "2") (pinfunction "OUT_2") (pintype "passive"))
    )
    (net (code "80") (name "Net-(DW300-K)") (class "Default")
      (node (ref "C19") (pin "1") (pinfunction "1_1") (pintype "passive"))
      (node (ref "DW300") (pin "2") (pinfunction "K_2") (pintype "passive"))
      (node (ref "L302") (pin "1") (pinfunction "1_1") (pintype "passive"))
      (node (ref "U300") (pin "8") (pinfunction "SW_8") (pintype "passive"))
    )
    (net (code "81") (name "Net-(L21-Pad1)") (class "Default")
      (node (ref "L21") (pin "1") (pinfunction "1_1") (pintype "passive"))
      (node (ref "Q21") (pin "2") (pinfunction "D_2") (pintype "passive"))
      (node (ref "Q21") (pin "4") (pinfunction "D_4") (pintype "passive"))
      (node (ref "R133") (pin "2") (pinfunction "2_2") (pintype "passive"))
    )
    (net (code "82") (name "Net-(Q8-Pad1)") (class "Default")
      (node (ref "Q8") (pin "1") (pintype "passive"))
      (node (ref "R171") (pin "1") (pinfunction "1_1") (pintype "passive"))
      (node (ref "R174") (pin "1") (pinfunction "1_1") (pintype "passive"))
    )
    (net (code "83") (name "Net-(Q8-Pad2)") (class "Default")
      (node (ref "Q8") (pin "2") (pintype "passive"))
      (node (ref "R169") (pin "2") (pinfunction "2_2") (pintype "passive"))
      (node (ref "R25") (pin "1") (pinfunction "1_1") (pintype "passive"))
    )
    (net (code "84") (name "Net-(Q11-B)") (class "Default")
      (node (ref "Q11") (pin "1") (pinfunction "B_1") (pintype "input"))
      (node (ref "R75") (pin "2") (pinfunction "2_2") (pintype "passive"))
      (node (ref "R78") (pin "1") (pinfunction "1_1") (pintype "passive"))
    )
    (net (code "85") (name "Net-(Q11-C)") (class "Default")
      (node (ref "DL10") (pin "2") (pinfunction "2_2") (pintype "passive"))
      (node (ref "DL11") (pin "2") (pinfunction "2_2") (pintype "passive"))
      (node (ref "DL8") (pin "2") (pinfunction "2_2") (pintype "passive"))
      (node (ref "DL9") (pin "2") (pinfunction "2_2") (pintype "passive"))
      (node (ref "Q11") (pin "3") (pinfunction "C_3") (pintype "passive"))
    )
    (net (code "86") (name "Net-(Q12-B)") (class "Default")
      (node (ref "Q12") (pin "1") (pinfunction "B_1") (pintype "input"))
      (node (ref "R76") (pin "2") (pinfunction "2_2") (pintype "passive"))
      (node (ref "R79") (pin "1") (pinfunction "1_1") (pintype "passive"))
    )
    (net (code "87") (name "Net-(Q12-C)") (class "Default")
      (node (ref "DL12") (pin "2") (pinfunction "2_2") (pintype "passive"))
      (node (ref "DL13") (pin "2") (pinfunction "2_2") (pintype "passive"))
      (node (ref "DL14") (pin "2") (pinfunction "2_2") (pintype "passive"))
      (node (ref "DL15") (pin "2") (pinfunction "2_2") (pintype "passive"))
      (node (ref "Q12") (pin "3") (pinfunction "C_3") (pintype "passive"))
    )
    (net (code "88") (name "Net-(Q19-b)") (class "Default")
      (node (ref "Q19") (pin "1") (pinfunction "b_1") (pintype "input"))
      (node (ref "R135") (pin "2") (pinfunction "2_2") (pintype "passive"))
      (node (ref "R136") (pin "2") (pinfunction "2_2") (pintype "passive"))
    )
    (net (code "89") (name "Net-(Q19-e)") (class "Default")
      (node (ref "Q19") (pin "3") (pinfunction "e_3") (pintype "passive"))
      (node (ref "Q21") (pin "1") (pinfunction "G_1") (pintype "passive"))
      (node (ref "R134") (pin "2") (pinfunction "2_2") (pintype "passive"))
    )
    (net (code "90") (name "Net-(Q20-out)") (class "Default")
      (node (ref "Q20") (pin "3") (pinfunction "out_3") (pintype "passive"))
      (node (ref "R130") (pin "2") (pinfunction "2_2") (pintype "passive"))
      (node (ref "U300") (pin "3") (pinfunction "EN_3") (pintype "passive"))
    )
    (net (code "91") (name "Net-(Q22-out)") (class "Default")
      (node (ref "Q22") (pin "3") (pinfunction "out_3") (pintype "passive"))
      (node (ref "R174") (pin "2") (pinfunction "2_2") (pintype "passive"))
    )
    (net (code "92") (name "Net-(Q26-Pad1)") (class "Default")
      (node (ref "Q26") (pin "1") (pintype "passive"))
      (node (ref "R102") (pin "1") (pinfunction "1_1") (pintype "passive"))
      (node (ref "R105") (pin "1") (pinfunction "1_1") (pintype "passive"))
    )
    (net (code "93") (name "Net-(Q26-Pad2)") (class "Default")
      (node (ref "Q26") (pin "2") (pintype "passive"))
      (node (ref "R22") (pin "1") (pinfunction "1_1") (pintype "passive"))
      (node (ref "R62") (pin "2") (pinfunction "2_2") (pintype "passive"))
    )
    (net (code "94") (name "Net-(Q27-out)") (class "Default")
      (node (ref "Q27") (pin "3") (pinfunction "out_3") (pintype "passive"))
      (node (ref "R105") (pin "2") (pinfunction "2_2") (pintype "passive"))
    )
    (net (code "95") (name "Net-(R196-Pad2)") (class "Default")
      (node (ref "R196") (pin "2") (pinfunction "2_2") (pintype "passive"))
      (node (ref "R197") (pin "1") (pinfunction "1_1") (pintype "passive"))
    )
    (net (code "96") (name "Net-(U3-VOUT)") (class "Default")
      (node (ref "C100") (pin "1") (pinfunction "1_1") (pintype "passive"))
      (node (ref "CP19") (pin "1") (pinfunction "1_1") (pintype "passive"))
      (node (ref "R178") (pin "1") (pinfunction "1_1") (pintype "passive"))
      (node (ref "U3") (pin "3") (pinfunction "VOUT_3") (pintype "passive"))
    )
    (net (code "97") (name "Net-(U300-BST)") (class "Default")
      (node (ref "C19") (pin "2") (pinfunction "2_2") (pintype "passive"))
      (node (ref "R162") (pin "1") (pinfunction "1_1") (pintype "passive"))
      (node (ref "U300") (pin "7") (pinfunction "BST_7") (pintype "passive"))
    )
    (net (code "98") (name "Net-(U300-FB)") (class "Default")
      (node (ref "R195") (pin "2") (pinfunction "2_2") (pintype "passive"))
      (node (ref "U300") (pin "4") (pinfunction "FB_4") (pintype "passive"))
    )
    (net (code "99") (name "Net-(U300-SS)") (class "Default")
      (node (ref "C49") (pin "2") (pinfunction "2_2") (pintype "passive"))
      (node (ref "U300") (pin "5") (pinfunction "SS_5") (pintype "passive"))
    )
    (net (code "100") (name "Net-(U300-VO)") (class "Default")
      (node (ref "R163") (pin "1") (pinfunction "1_1") (pintype "passive"))
      (node (ref "R179") (pin "2") (pinfunction "2_2") (pintype "passive"))
      (node (ref "U300") (pin "6") (pinfunction "VO_6") (pintype "passive"))
    )
    (net (code "101") (name "V") (class "Default")
      (node (ref "C104") (pin "2") (pinfunction "2_2") (pintype "passive"))
      (node (ref "C106") (pin "2") (pinfunction "2_2") (pintype "passive"))
      (node (ref "C107") (pin "2") (pinfunction "2_2") (pintype "passive"))
      (node (ref "C2") (pin "2") (pinfunction "2_2") (pintype "passive"))
      (node (ref "C83") (pin "2") (pinfunction "2_2") (pintype "passive"))
      (node (ref "CP1") (pin "1") (pinfunction "1_1") (pintype "passive"))
      (node (ref "CP15") (pin "1") (pinfunction "1_1") (pintype "passive"))
      (node (ref "D2") (pin "1") (pinfunction "1_1") (pintype "passive"))
      (node (ref "D7") (pin "2") (pinfunction "K_2") (pintype "passive"))
      (node (ref "L4") (pin "1") (pinfunction "1_1") (pintype "passive"))
      (node (ref "R176") (pin "1") (pinfunction "1_1") (pintype "passive"))
    )
    (net (code "102") (name "unconnected-(DZ15-Pad5)") (class "Default")
      (node (ref "DZ15") (pin "5") (pintype "passive"))
    )
    (net (code "103") (name "unconnected-(LOGO-Pad1)") (class "Default")
      (node (ref "LOGO") (pin "1") (pinfunction "1_1") (pintype "passive"))
    )
    (net (code "104") (name "unconnected-(TP1-Pad1)") (class "Default")
      (node (ref "TP1") (pin "1") (pinfunction "1_1") (pintype "passive"))
    )
    (net (code "105") (name "unconnected-(TP2-Pad1)") (class "Default")
      (node (ref "TP2") (pin "1") (pinfunction "1_1") (pintype "passive"))
    )
    (net (code "106") (name "unconnected-(TP3-Pad1)") (class "Default")
      (node (ref "TP3") (pin "1") (pinfunction "1_1") (pintype "passive"))
    )
    (net (code "107") (name "unconnected-(TP4-Pad1)") (class "Default")
      (node (ref "TP4") (pin "1") (pinfunction "1_1") (pintype "passive"))
    )
  )
)
